# ET-USB.net
KiCad netlist of a schematic drawn in Altium Designer
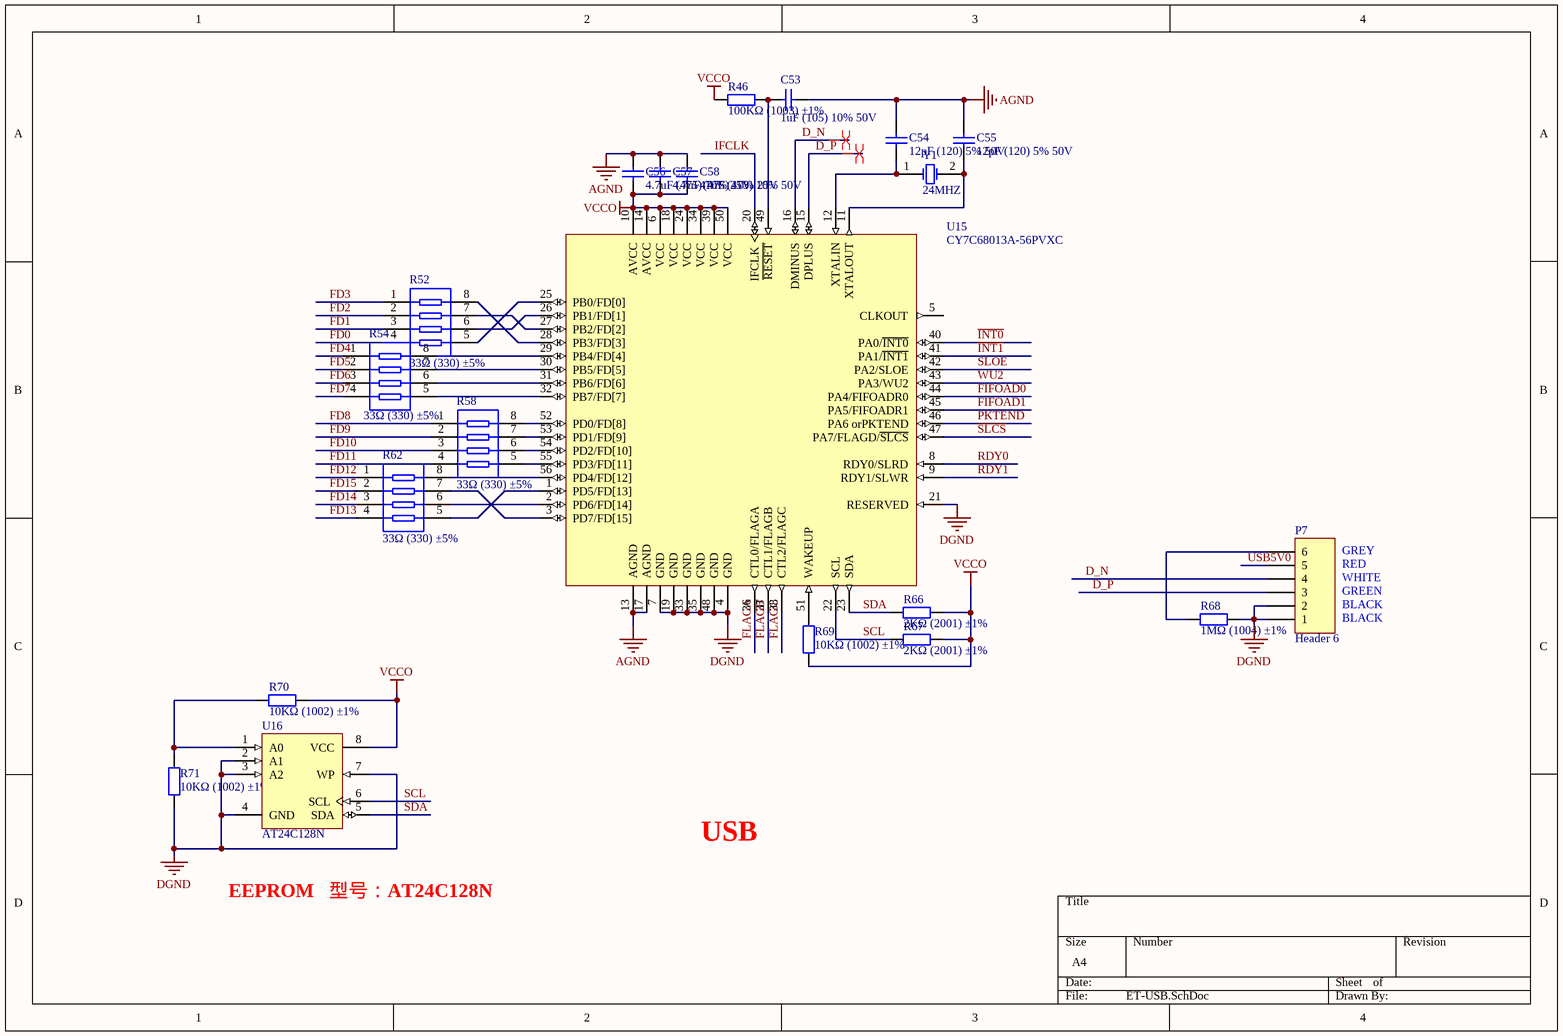
[diagram p0: ET-USB.SchDoc]

(export (version "E")
  (design (tool "Eeschema 10.0.6"))
  (components
    (comp (ref "C53")
      (value "1uF (105) 10% 50V")
      (footprint "LC-0805_C")
      (description "贴片电容")
      (libsource (lib "Miscellaneous Devices LC") (part "0805 1uF (105) 10% 50V"))
    )
    (comp (ref "C54")
      (value "12pF (120) 5% 50V")
      (footprint "LC-0805_C")
      (description "贴片电容")
      (libsource (lib "Miscellaneous Devices LC") (part "0805 12pF (120) 5% 50V"))
    )
    (comp (ref "C55")
      (value "12pF (120) 5% 50V")
      (footprint "LC-0805_C")
      (description "贴片电容")
      (libsource (lib "Miscellaneous Devices LC") (part "0805 12pF (120) 5% 50V"))
    )
    (comp (ref "C56")
      (value "4.7uF (475) 10% 25V")
      (footprint "LC-0805_C")
      (description "贴片电容")
      (libsource (lib "Miscellaneous Devices LC") (part "0805 4.7uF (475) 10% 25V"))
    )
    (comp (ref "C57")
      (value "4.7uF (475) 10% 25V")
      (footprint "LC-0805_C")
      (description "贴片电容")
      (libsource (lib "Miscellaneous Devices LC") (part "0805 4.7uF (475) 10% 25V"))
    )
    (comp (ref "C58")
      (value "47nF (473) 10% 50V")
      (footprint "LC-0805_C")
      (description "贴片电容")
      (libsource (lib "Miscellaneous Devices LC") (part "0805 47nF (473) 10% 50V"))
    )
    (comp (ref "P7")
      (value "Header 6")
      (footprint "HDR1X6")
      (description "Header, 6-Pin")
      (fields (field (name "PUBLISHER") "Altium Limited"))
      (libsource (lib "Miscellaneous Connectors") (part "Header 6"))
    )
    (comp (ref "R46")
      (value "100KΩ (1003) ±1%")
      (footprint "LC-0805_R")
      (description "贴片电阻")
      (libsource (lib "Miscellaneous Devices LC") (part "0805 100KΩ (1003) 1%"))
    )
    (comp (ref "R52")
      (value "33Ω (330) ±5%")
      (footprint "LC-0402_Rx4")
      (description "贴片排阻")
      (libsource (lib "Miscellaneous Devices LC") (part "0402*4 33Ω (330) 5%"))
    )
    (comp (ref "R54")
      (value "33Ω (330) ±5%")
      (footprint "LC-0402_Rx4")
      (description "贴片排阻")
      (libsource (lib "Miscellaneous Devices LC") (part "0402*4 33Ω (330) 5%"))
    )
    (comp (ref "R58")
      (value "33Ω (330) ±5%")
      (footprint "LC-0402_Rx4")
      (description "贴片排阻")
      (libsource (lib "Miscellaneous Devices LC") (part "0402*4 33Ω (330) 5%"))
    )
    (comp (ref "R62")
      (value "33Ω (330) ±5%")
      (footprint "LC-0402_Rx4")
      (description "贴片排阻")
      (libsource (lib "Miscellaneous Devices LC") (part "0402*4 33Ω (330) 5%"))
    )
    (comp (ref "R66")
      (value "2KΩ (2001) ±1%")
      (footprint "LC-0805_R")
      (description "贴片电阻")
      (libsource (lib "Miscellaneous Devices LC") (part "0805 2KΩ (2001) 1%"))
    )
    (comp (ref "R67")
      (value "2KΩ (2001) ±1%")
      (footprint "LC-0805_R")
      (description "贴片电阻")
      (libsource (lib "Miscellaneous Devices LC") (part "0805 2KΩ (2001) 1%"))
    )
    (comp (ref "R68")
      (value "1MΩ (1004) ±1%")
      (footprint "LC-0805_R")
      (description "贴片电阻")
      (libsource (lib "Miscellaneous Devices LC") (part "0805 1MΩ (1004) 1%"))
    )
    (comp (ref "R69")
      (value "10KΩ (1002) ±1%")
      (footprint "LC-0805_R")
      (description "贴片电阻")
      (libsource (lib "Miscellaneous Devices LC") (part "0805 10KΩ (1002) 1%"))
    )
    (comp (ref "R70")
      (value "10KΩ (1002) ±1%")
      (footprint "LC-0805_R")
      (description "贴片电阻")
      (libsource (lib "") (part "0805 10KΩ (1002) 1%_1"))
    )
    (comp (ref "R71")
      (value "10KΩ (1002) ±1%")
      (footprint "LC-0805_R")
      (description "贴片电阻")
      (libsource (lib "Miscellaneous Devices LC") (part "0805 10KΩ (1002) 1%"))
    )
    (comp (ref "U15")
      (value "CY7C68013A-56PVXC")
      (footprint "O56_N")
      (fields (field (name "PUBLISHER") "Altium Limited"))
      (libsource (lib "Cypress USB High-Speed") (part "CY7C68013A-56PVXC"))
    )
    (comp (ref "U16")
      (value "AT24C128N")
      (footprint "8P3")
      (description "1Kbit (128 x 8), 2-wire Bus Automotive Serial EEPROM with Write Protect, 2.5V, 8-Pin TSSOP, Bulk")
      (fields (field (name "PUBLISHER") "Altium Limited"))
      (libsource (lib "Atmel Memory Serial EEPROM") (part "AT24C128N"))
    )
    (comp (ref "Y1")
      (value "24MHZ")
      (footprint "XTAL5")
      (description "Crystal Oscillator")
      (fields (field (name "PUBLISHER") "Altium Limited"))
      (libsource (lib "晶振封装") (part "XTAL"))
    )
  )
  (nets
    (net (code "2") (name "/D_N") (class "Default")
      (node (ref "P7") (pin "4") (pinfunction "4_4") (pintype "passive"))
      (node (ref "U15") (pin "16") (pinfunction "DMINUS_16") (pintype "bidirectional"))
    )
    (net (code "3") (name "/D_P") (class "Default")
      (node (ref "P7") (pin "3") (pinfunction "3_3") (pintype "passive"))
      (node (ref "U15") (pin "15") (pinfunction "DPLUS_15") (pintype "bidirectional"))
    )
    (net (code "4") (name "/FD0") (class "Default")
      (node (ref "R52") (pin "4") (pinfunction "4_4") (pintype "passive"))
    )
    (net (code "5") (name "/FD1") (class "Default")
      (node (ref "R52") (pin "3") (pinfunction "3_3") (pintype "passive"))
    )
    (net (code "6") (name "/FD2") (class "Default")
      (node (ref "R52") (pin "2") (pinfunction "2_2") (pintype "passive"))
    )
    (net (code "7") (name "/FD3") (class "Default")
      (node (ref "R52") (pin "1") (pinfunction "1_1") (pintype "passive"))
    )
    (net (code "8") (name "/FD4") (class "Default")
      (node (ref "R54") (pin "1") (pinfunction "1_1") (pintype "passive"))
    )
    (net (code "9") (name "/FD5") (class "Default")
      (node (ref "R54") (pin "2") (pinfunction "2_2") (pintype "passive"))
    )
    (net (code "10") (name "/FD6") (class "Default")
      (node (ref "R54") (pin "3") (pinfunction "3_3") (pintype "passive"))
    )
    (net (code "11") (name "/FD7") (class "Default")
      (node (ref "R54") (pin "4") (pinfunction "4_4") (pintype "passive"))
    )
    (net (code "12") (name "/FD8") (class "Default")
      (node (ref "R58") (pin "1") (pinfunction "1_1") (pintype "passive"))
    )
    (net (code "13") (name "/FD9") (class "Default")
      (node (ref "R58") (pin "2") (pinfunction "2_2") (pintype "passive"))
    )
    (net (code "14") (name "/FD10") (class "Default")
      (node (ref "R58") (pin "3") (pinfunction "3_3") (pintype "passive"))
    )
    (net (code "15") (name "/FD11") (class "Default")
      (node (ref "R58") (pin "4") (pinfunction "4_4") (pintype "passive"))
    )
    (net (code "16") (name "/FD12") (class "Default")
      (node (ref "R62") (pin "1") (pinfunction "1_1") (pintype "passive"))
    )
    (net (code "17") (name "/FD13") (class "Default")
      (node (ref "R62") (pin "4") (pinfunction "4_4") (pintype "passive"))
    )
    (net (code "18") (name "/FD14") (class "Default")
      (node (ref "R62") (pin "3") (pinfunction "3_3") (pintype "passive"))
    )
    (net (code "19") (name "/FD15") (class "Default")
      (node (ref "R62") (pin "2") (pinfunction "2_2") (pintype "passive"))
    )
    (net (code "20") (name "/FIFOAD0") (class "Default")
      (node (ref "U15") (pin "44") (pinfunction "PA4/FIFOADR0_44") (pintype "bidirectional"))
    )
    (net (code "21") (name "/FIFOAD1") (class "Default")
      (node (ref "U15") (pin "45") (pinfunction "PA5/FIFOADR1_45") (pintype "bidirectional"))
    )
    (net (code "22") (name "/FLAGA") (class "Default")
      (node (ref "U15") (pin "36") (pinfunction "CTL0/FLAGA_36") (pintype "output"))
    )
    (net (code "23") (name "/FLAGB") (class "Default")
      (node (ref "U15") (pin "37") (pinfunction "CTL1/FLAGB_37") (pintype "output"))
    )
    (net (code "24") (name "/FLAGC") (class "Default")
      (node (ref "U15") (pin "38") (pinfunction "CTL2/FLAGC_38") (pintype "output"))
    )
    (net (code "27") (name "/IFCLK") (class "Default")
      (node (ref "U15") (pin "20") (pinfunction "IFCLK_20") (pintype "bidirectional"))
    )
    (net (code "28") (name "/PKTEND") (class "Default")
      (node (ref "U15") (pin "46") (pinfunction "PA6_orPKTEND_46") (pintype "bidirectional"))
    )
    (net (code "29") (name "/RDY0") (class "Default")
      (node (ref "U15") (pin "8") (pinfunction "RDY0/SLRD_8") (pintype "input"))
    )
    (net (code "30") (name "/RDY1") (class "Default")
      (node (ref "U15") (pin "9") (pinfunction "RDY1/SLWR_9") (pintype "input"))
    )
    (net (code "32") (name "/SCL") (class "Default")
      (node (ref "R67") (pin "1") (pinfunction "1_1") (pintype "passive"))
      (node (ref "U15") (pin "22") (pinfunction "SCL_22") (pintype "output"))
      (node (ref "U16") (pin "6") (pinfunction "SCL_6") (pintype "input"))
    )
    (net (code "33") (name "/SDA") (class "Default")
      (node (ref "R66") (pin "1") (pinfunction "1_1") (pintype "passive"))
      (node (ref "U15") (pin "23") (pinfunction "SDA_23") (pintype "output"))
      (node (ref "U16") (pin "5") (pinfunction "SDA_5") (pintype "bidirectional"))
    )
    (net (code "34") (name "/SLOE") (class "Default")
      (node (ref "U15") (pin "42") (pinfunction "PA2/SLOE_42") (pintype "bidirectional"))
    )
    (net (code "35") (name "/USB5V0") (class "Default")
      (node (ref "P7") (pin "5") (pinfunction "5_5") (pintype "passive"))
    )
    (net (code "37") (name "/WU2") (class "Default")
      (node (ref "U15") (pin "43") (pinfunction "PA3/WU2_43") (pintype "bidirectional"))
    )
    (net (code "38") (name "/~{INT0}") (class "Default")
      (node (ref "U15") (pin "40") (pinfunction "PA0/~{INT0}_40") (pintype "bidirectional"))
    )
    (net (code "39") (name "/~{INT1}") (class "Default")
      (node (ref "U15") (pin "41") (pinfunction "PA1/~{INT1}_41") (pintype "bidirectional"))
    )
    (net (code "40") (name "/~{SLCS}") (class "Default")
      (node (ref "U15") (pin "47") (pinfunction "PA7/FLAGD/~{SLCS}_47") (pintype "bidirectional"))
    )
    (net (code "41") (name "AGND") (class "Default")
      (node (ref "C53") (pin "2") (pinfunction "2_2") (pintype "passive"))
      (node (ref "C54") (pin "2") (pinfunction "2_2") (pintype "passive"))
      (node (ref "C55") (pin "2") (pinfunction "2_2") (pintype "passive"))
      (node (ref "C56") (pin "2") (pinfunction "2_2") (pintype "passive"))
      (node (ref "C57") (pin "2") (pinfunction "2_2") (pintype "passive"))
      (node (ref "C58") (pin "2") (pinfunction "2_2") (pintype "passive"))
      (node (ref "U15") (pin "13") (pinfunction "AGND_13") (pintype "power_in"))
      (node (ref "U15") (pin "17") (pinfunction "AGND_17") (pintype "power_in"))
    )
    (net (code "42") (name "DGND") (class "Default")
      (node (ref "P7") (pin "1") (pinfunction "1_1") (pintype "passive"))
      (node (ref "P7") (pin "2") (pinfunction "2_2") (pintype "passive"))
      (node (ref "R68") (pin "2") (pinfunction "2_2") (pintype "passive"))
      (node (ref "R71") (pin "1") (pinfunction "1_1") (pintype "passive"))
      (node (ref "U15") (pin "19") (pinfunction "GND_19") (pintype "power_in"))
      (node (ref "U15") (pin "21") (pinfunction "RESERVED_21") (pintype "input"))
      (node (ref "U15") (pin "33") (pinfunction "GND_33") (pintype "power_in"))
      (node (ref "U15") (pin "35") (pinfunction "GND_35") (pintype "power_in"))
      (node (ref "U15") (pin "4") (pinfunction "GND_4") (pintype "power_in"))
      (node (ref "U15") (pin "48") (pinfunction "GND_48") (pintype "power_in"))
      (node (ref "U15") (pin "7") (pinfunction "GND_7") (pintype "power_in"))
      (node (ref "U16") (pin "2") (pinfunction "A1_2") (pintype "input"))
      (node (ref "U16") (pin "3") (pinfunction "A2_3") (pintype "input"))
      (node (ref "U16") (pin "4") (pinfunction "GND_4") (pintype "power_in"))
      (node (ref "U16") (pin "7") (pinfunction "WP_7") (pintype "input"))
    )
    (net (code "43") (name "Net-(P7-Pad6)") (class "Default")
      (node (ref "P7") (pin "6") (pinfunction "6_6") (pintype "passive"))
      (node (ref "R68") (pin "1") (pinfunction "1_1") (pintype "passive"))
    )
    (net (code "44") (name "Net-(U15-PB0{slash}FD[0])") (class "Default")
      (node (ref "R52") (pin "5") (pinfunction "5_5") (pintype "passive"))
      (node (ref "U15") (pin "25") (pinfunction "PB0/FD[0]_25") (pintype "bidirectional"))
    )
    (net (code "45") (name "Net-(U15-PB1{slash}FD[1])") (class "Default")
      (node (ref "R52") (pin "6") (pinfunction "6_6") (pintype "passive"))
      (node (ref "U15") (pin "26") (pinfunction "PB1/FD[1]_26") (pintype "bidirectional"))
    )
    (net (code "46") (name "Net-(U15-PB2{slash}FD[2])") (class "Default")
      (node (ref "R52") (pin "7") (pinfunction "7_7") (pintype "passive"))
      (node (ref "U15") (pin "27") (pinfunction "PB2/FD[2]_27") (pintype "bidirectional"))
    )
    (net (code "47") (name "Net-(U15-PB3{slash}FD[3])") (class "Default")
      (node (ref "R52") (pin "8") (pinfunction "8_8") (pintype "passive"))
      (node (ref "U15") (pin "28") (pinfunction "PB3/FD[3]_28") (pintype "bidirectional"))
    )
    (net (code "48") (name "Net-(U15-PB4{slash}FD[4])") (class "Default")
      (node (ref "R54") (pin "8") (pinfunction "8_8") (pintype "passive"))
      (node (ref "U15") (pin "29") (pinfunction "PB4/FD[4]_29") (pintype "bidirectional"))
    )
    (net (code "49") (name "Net-(U15-PB5{slash}FD[5])") (class "Default")
      (node (ref "R54") (pin "7") (pinfunction "7_7") (pintype "passive"))
      (node (ref "U15") (pin "30") (pinfunction "PB5/FD[5]_30") (pintype "bidirectional"))
    )
    (net (code "50") (name "Net-(U15-PB6{slash}FD[6])") (class "Default")
      (node (ref "R54") (pin "6") (pinfunction "6_6") (pintype "passive"))
      (node (ref "U15") (pin "31") (pinfunction "PB6/FD[6]_31") (pintype "bidirectional"))
    )
    (net (code "51") (name "Net-(U15-PB7{slash}FD[7])") (class "Default")
      (node (ref "R54") (pin "5") (pinfunction "5_5") (pintype "passive"))
      (node (ref "U15") (pin "32") (pinfunction "PB7/FD[7]_32") (pintype "bidirectional"))
    )
    (net (code "52") (name "Net-(U15-PD0{slash}FD[8])") (class "Default")
      (node (ref "R58") (pin "8") (pinfunction "8_8") (pintype "passive"))
      (node (ref "U15") (pin "52") (pinfunction "PD0/FD[8]_52") (pintype "bidirectional"))
    )
    (net (code "53") (name "Net-(U15-PD1{slash}FD[9])") (class "Default")
      (node (ref "R58") (pin "7") (pinfunction "7_7") (pintype "passive"))
      (node (ref "U15") (pin "53") (pinfunction "PD1/FD[9]_53") (pintype "bidirectional"))
    )
    (net (code "54") (name "Net-(U15-PD2{slash}FD[10])") (class "Default")
      (node (ref "R58") (pin "6") (pinfunction "6_6") (pintype "passive"))
      (node (ref "U15") (pin "54") (pinfunction "PD2/FD[10]_54") (pintype "bidirectional"))
    )
    (net (code "55") (name "Net-(U15-PD3{slash}FD[11])") (class "Default")
      (node (ref "R58") (pin "5") (pinfunction "5_5") (pintype "passive"))
      (node (ref "U15") (pin "55") (pinfunction "PD3/FD[11]_55") (pintype "bidirectional"))
    )
    (net (code "56") (name "Net-(U15-PD4{slash}FD[12])") (class "Default")
      (node (ref "R62") (pin "8") (pinfunction "8_8") (pintype "passive"))
      (node (ref "U15") (pin "56") (pinfunction "PD4/FD[12]_56") (pintype "bidirectional"))
    )
    (net (code "57") (name "Net-(U15-PD5{slash}FD[13])") (class "Default")
      (node (ref "R62") (pin "5") (pinfunction "5_5") (pintype "passive"))
      (node (ref "U15") (pin "1") (pinfunction "PD5/FD[13]_1") (pintype "bidirectional"))
    )
    (net (code "58") (name "Net-(U15-PD6{slash}FD[14])") (class "Default")
      (node (ref "R62") (pin "6") (pinfunction "6_6") (pintype "passive"))
      (node (ref "U15") (pin "2") (pinfunction "PD6/FD[14]_2") (pintype "bidirectional"))
    )
    (net (code "59") (name "Net-(U15-PD7{slash}FD[15])") (class "Default")
      (node (ref "R62") (pin "7") (pinfunction "7_7") (pintype "passive"))
      (node (ref "U15") (pin "3") (pinfunction "PD7/FD[15]_3") (pintype "bidirectional"))
    )
    (net (code "60") (name "Net-(U15-WAKEUP)") (class "Default")
      (node (ref "R69") (pin "2") (pinfunction "2_2") (pintype "passive"))
      (node (ref "U15") (pin "51") (pinfunction "WAKEUP_51") (pintype "input"))
    )
    (net (code "61") (name "Net-(U15-XTALIN)") (class "Default")
      (node (ref "C54") (pin "1") (pinfunction "1_1") (pintype "passive"))
      (node (ref "U15") (pin "12") (pinfunction "XTALIN_12") (pintype "input"))
      (node (ref "Y1") (pin "1") (pinfunction "OSC1_1") (pintype "passive"))
    )
    (net (code "62") (name "Net-(U15-XTALOUT)") (class "Default")
      (node (ref "C55") (pin "1") (pinfunction "1_1") (pintype "passive"))
      (node (ref "U15") (pin "11") (pinfunction "XTALOUT_11") (pintype "output"))
      (node (ref "Y1") (pin "2") (pinfunction "OSC2_2") (pintype "passive"))
    )
    (net (code "63") (name "Net-(U15-~{RESET})") (class "Default")
      (node (ref "C53") (pin "1") (pinfunction "1_1") (pintype "passive"))
      (node (ref "R46") (pin "2") (pinfunction "2_2") (pintype "passive"))
      (node (ref "U15") (pin "49") (pinfunction "~{RESET}_49") (pintype "input"))
    )
    (net (code "64") (name "Net-(U16-A0)") (class "Default")
      (node (ref "R70") (pin "1") (pinfunction "1_1") (pintype "passive"))
      (node (ref "R71") (pin "2") (pinfunction "2_2") (pintype "passive"))
      (node (ref "U16") (pin "1") (pinfunction "A0_1") (pintype "input"))
    )
    (net (code "65") (name "VCCO") (class "Default")
      (node (ref "C56") (pin "1") (pinfunction "1_1") (pintype "passive"))
      (node (ref "C57") (pin "1") (pinfunction "1_1") (pintype "passive"))
      (node (ref "C58") (pin "1") (pinfunction "1_1") (pintype "passive"))
      (node (ref "R46") (pin "1") (pinfunction "1_1") (pintype "passive"))
      (node (ref "R66") (pin "2") (pinfunction "2_2") (pintype "passive"))
      (node (ref "R67") (pin "2") (pinfunction "2_2") (pintype "passive"))
      (node (ref "R69") (pin "1") (pinfunction "1_1") (pintype "passive"))
      (node (ref "R70") (pin "2") (pinfunction "2_2") (pintype "passive"))
      (node (ref "U15") (pin "10") (pinfunction "AVCC_10") (pintype "power_in"))
      (node (ref "U15") (pin "14") (pinfunction "AVCC_14") (pintype "power_in"))
      (node (ref "U15") (pin "18") (pinfunction "VCC_18") (pintype "power_in"))
      (node (ref "U15") (pin "24") (pinfunction "VCC_24") (pintype "power_in"))
      (node (ref "U15") (pin "34") (pinfunction "VCC_34") (pintype "power_in"))
      (node (ref "U15") (pin "39") (pinfunction "VCC_39") (pintype "power_in"))
      (node (ref "U15") (pin "50") (pinfunction "VCC_50") (pintype "power_in"))
      (node (ref "U15") (pin "6") (pinfunction "VCC_6") (pintype "power_in"))
      (node (ref "U16") (pin "8") (pinfunction "VCC_8") (pintype "power_in"))
    )
    (net (code "66") (name "unconnected-(U15-CLKOUT-Pad5)") (class "Default")
      (node (ref "U15") (pin "5") (pinfunction "CLKOUT_5") (pintype "output"))
    )
  )
)
